# DAC2.net
KiCad netlist of a schematic drawn in EAGLE
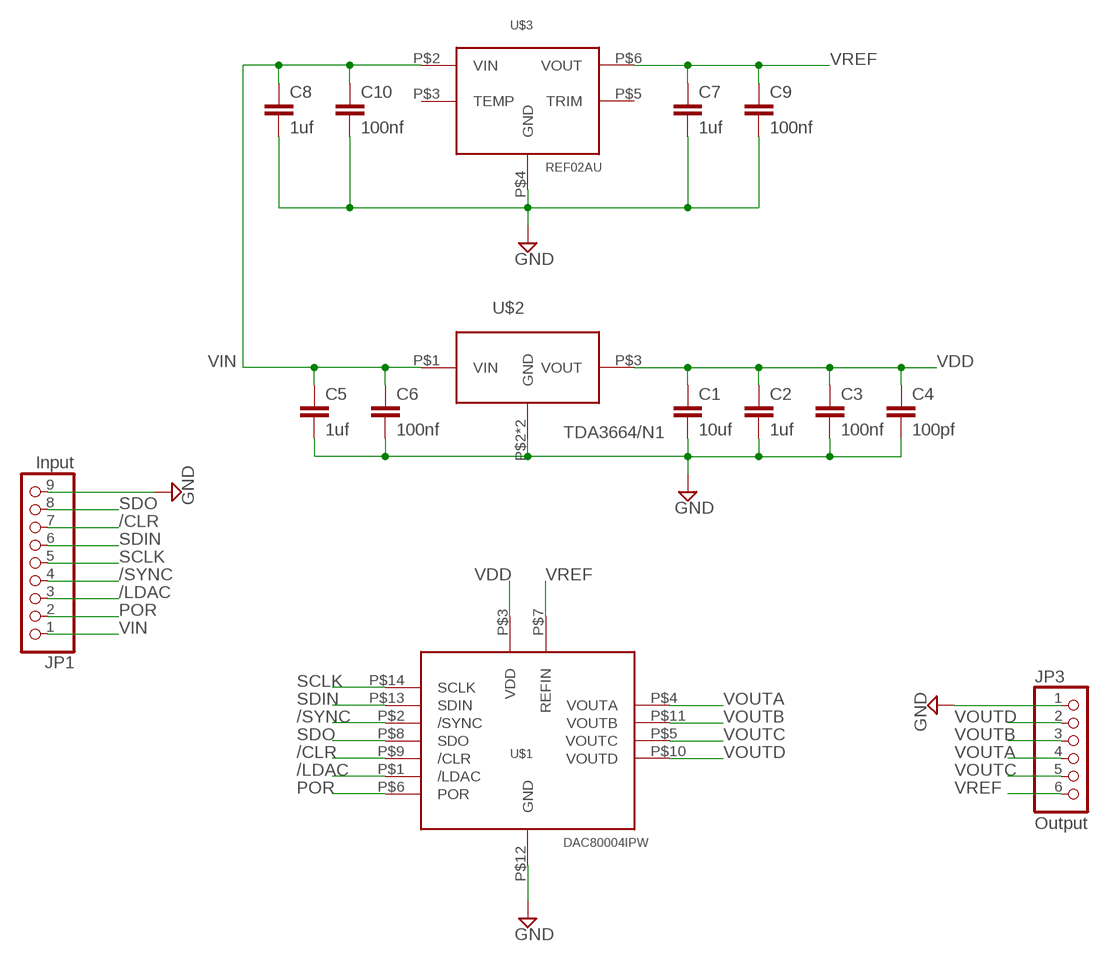
[diagram p0: schematic, sheet 1]

(export (version "E")
  (design (tool "Eeschema 10.0.6"))
  (components
    (comp (ref "C1")
      (value "10uf")
      (footprint "eagle-import:C1210")
      (libsource (lib "eagle-import") (part "C-EUC1210"))
    )
    (comp (ref "C2")
      (value "1uf")
      (footprint "eagle-import:C0603")
      (libsource (lib "eagle-import") (part "C-EUC0603"))
    )
    (comp (ref "C3")
      (value "100nf")
      (footprint "eagle-import:C0603")
      (libsource (lib "eagle-import") (part "C-EUC0603"))
    )
    (comp (ref "C4")
      (value "100pf")
      (footprint "eagle-import:C0603")
      (libsource (lib "eagle-import") (part "C-EUC0603"))
    )
    (comp (ref "C5")
      (value "1uf")
      (footprint "eagle-import:C0603")
      (libsource (lib "eagle-import") (part "C-EUC0603"))
    )
    (comp (ref "C6")
      (value "100nf")
      (footprint "eagle-import:C0603")
      (libsource (lib "eagle-import") (part "C-EUC0603"))
    )
    (comp (ref "C7")
      (value "1uf")
      (footprint "eagle-import:C0603")
      (libsource (lib "eagle-import") (part "C-EUC0603"))
    )
    (comp (ref "C8")
      (value "1uf")
      (footprint "eagle-import:C0603")
      (libsource (lib "eagle-import") (part "C-EUC0603"))
    )
    (comp (ref "C9")
      (value "100nf")
      (footprint "eagle-import:C0603")
      (libsource (lib "eagle-import") (part "C-EUC0603"))
    )
    (comp (ref "C10")
      (value "100nf")
      (footprint "eagle-import:C0603")
      (libsource (lib "eagle-import") (part "C-EUC0603"))
    )
    (comp (ref "JP1")
      (value "Input")
      (footprint "eagle-import:1X09")
      (libsource (lib "eagle-import") (part "PINHD-1X9"))
    )
    (comp (ref "JP3")
      (value "Output")
      (footprint "eagle-import:1X06")
      (libsource (lib "eagle-import") (part "PINHD-1X6"))
    )
    (comp (ref "U$1")
      (value "DAC80004IPW")
      (footprint "eagle-import:TSSOP14")
      (libsource (lib "eagle-import") (part "DAC80004IPW"))
    )
    (comp (ref "U$2")
      (value "TDA3664/N1")
      (footprint "eagle-import:SOT223")
      (libsource (lib "eagle-import") (part "TDA3664/N1"))
    )
    (comp (ref "U$3")
      (value "REF02AU")
      (footprint "eagle-import:SO8")
      (libsource (lib "eagle-import") (part "REF02AU"))
    )
  )
  (nets
    (net (code "1") (name "/POR") (class "Default")
      (node (ref "JP1") (pin "2") (pinfunction "2_2") (pintype "passive"))
      (node (ref "U$1") (pin "P$6") (pinfunction "POR_P$6") (pintype "input"))
    )
    (net (code "2") (name "/SCLK") (class "Default")
      (node (ref "JP1") (pin "5") (pinfunction "5_5") (pintype "passive"))
      (node (ref "U$1") (pin "P$14") (pinfunction "SCLK_P$14") (pintype "input"))
    )
    (net (code "3") (name "/SDIN") (class "Default")
      (node (ref "JP1") (pin "6") (pinfunction "6_6") (pintype "passive"))
      (node (ref "U$1") (pin "P$13") (pinfunction "SDIN_P$13") (pintype "input"))
    )
    (net (code "4") (name "/SDO") (class "Default")
      (node (ref "JP1") (pin "8") (pinfunction "8_8") (pintype "passive"))
      (node (ref "U$1") (pin "P$8") (pinfunction "SDO_P$8") (pintype "output"))
    )
    (net (code "5") (name "/VDD") (class "Default")
      (node (ref "C1") (pin "1") (pinfunction "1_1") (pintype "passive"))
      (node (ref "C2") (pin "1") (pinfunction "1_1") (pintype "passive"))
      (node (ref "C3") (pin "1") (pinfunction "1_1") (pintype "passive"))
      (node (ref "C4") (pin "1") (pinfunction "1_1") (pintype "passive"))
      (node (ref "U$1") (pin "P$3") (pinfunction "VDD_P$3") (pintype "power_in"))
      (node (ref "U$2") (pin "P$3") (pinfunction "VOUT_P$3") (pintype "output"))
    )
    (net (code "6") (name "/VIN") (class "Default")
      (node (ref "C10") (pin "1") (pinfunction "1_1") (pintype "passive"))
      (node (ref "C5") (pin "1") (pinfunction "1_1") (pintype "passive"))
      (node (ref "C6") (pin "1") (pinfunction "1_1") (pintype "passive"))
      (node (ref "C8") (pin "1") (pinfunction "1_1") (pintype "passive"))
      (node (ref "JP1") (pin "1") (pinfunction "1_1") (pintype "passive"))
      (node (ref "U$2") (pin "P$1") (pinfunction "VIN_P$1") (pintype "power_in"))
      (node (ref "U$3") (pin "P$2") (pinfunction "VIN_P$2") (pintype "power_in"))
    )
    (net (code "7") (name "/VOUTA") (class "Default")
      (node (ref "JP3") (pin "4") (pinfunction "4_4") (pintype "passive"))
      (node (ref "U$1") (pin "P$4") (pinfunction "VOUTA_P$4") (pintype "output"))
    )
    (net (code "8") (name "/VOUTB") (class "Default")
      (node (ref "JP3") (pin "3") (pinfunction "3_3") (pintype "passive"))
      (node (ref "U$1") (pin "P$11") (pinfunction "VOUTB_P$11") (pintype "output"))
    )
    (net (code "9") (name "/VOUTC") (class "Default")
      (node (ref "JP3") (pin "5") (pinfunction "5_5") (pintype "passive"))
      (node (ref "U$1") (pin "P$5") (pinfunction "VOUTC_P$5") (pintype "output"))
    )
    (net (code "10") (name "/VOUTD") (class "Default")
      (node (ref "JP3") (pin "2") (pinfunction "2_2") (pintype "passive"))
      (node (ref "U$1") (pin "P$10") (pinfunction "VOUTD_P$10") (pintype "output"))
    )
    (net (code "11") (name "/VREF") (class "Default")
      (node (ref "C7") (pin "1") (pinfunction "1_1") (pintype "passive"))
      (node (ref "C9") (pin "1") (pinfunction "1_1") (pintype "passive"))
      (node (ref "JP3") (pin "6") (pinfunction "6_6") (pintype "passive"))
      (node (ref "U$1") (pin "P$7") (pinfunction "REFIN_P$7") (pintype "input"))
      (node (ref "U$3") (pin "P$6") (pinfunction "VOUT_P$6") (pintype "output"))
    )
    (net (code "12") (name "/{slash}CLR") (class "Default")
      (node (ref "JP1") (pin "7") (pinfunction "7_7") (pintype "passive"))
      (node (ref "U$1") (pin "P$9") (pinfunction "/CLR_P$9") (pintype "input"))
    )
    (net (code "13") (name "/{slash}LDAC") (class "Default")
      (node (ref "JP1") (pin "3") (pinfunction "3_3") (pintype "passive"))
      (node (ref "U$1") (pin "P$1") (pinfunction "/LDAC_P$1") (pintype "input"))
    )
    (net (code "14") (name "/{slash}SYNC") (class "Default")
      (node (ref "JP1") (pin "4") (pinfunction "4_4") (pintype "passive"))
      (node (ref "U$1") (pin "P$2") (pinfunction "/SYNC_P$2") (pintype "input"))
    )
    (net (code "15") (name "GND") (class "Default")
      (node (ref "C1") (pin "2") (pinfunction "2_2") (pintype "passive"))
      (node (ref "C10") (pin "2") (pinfunction "2_2") (pintype "passive"))
      (node (ref "C2") (pin "2") (pinfunction "2_2") (pintype "passive"))
      (node (ref "C3") (pin "2") (pinfunction "2_2") (pintype "passive"))
      (node (ref "C4") (pin "2") (pinfunction "2_2") (pintype "passive"))
      (node (ref "C5") (pin "2") (pinfunction "2_2") (pintype "passive"))
      (node (ref "C6") (pin "2") (pinfunction "2_2") (pintype "passive"))
      (node (ref "C7") (pin "2") (pinfunction "2_2") (pintype "passive"))
      (node (ref "C8") (pin "2") (pinfunction "2_2") (pintype "passive"))
      (node (ref "C9") (pin "2") (pinfunction "2_2") (pintype "passive"))
      (node (ref "JP1") (pin "9") (pinfunction "9_9") (pintype "passive"))
      (node (ref "JP3") (pin "1") (pinfunction "1_1") (pintype "passive"))
      (node (ref "U$1") (pin "P$12") (pinfunction "GND_P$12") (pintype "power_in"))
      (node (ref "U$2") (pin "P$2") (pinfunction "GND_P$2") (pintype "power_in"))
      (node (ref "U$2") (pin "P$4") (pinfunction "GND_P$4") (pintype "power_in"))
      (node (ref "U$3") (pin "P$4") (pinfunction "GND_P$4") (pintype "power_in"))
    )
    (net (code "16") (name "unconnected-(U$3-TEMP-PadP$3)") (class "Default")
      (node (ref "U$3") (pin "P$3") (pinfunction "TEMP_P$3") (pintype "bidirectional"))
    )
    (net (code "17") (name "unconnected-(U$3-TRIM-PadP$5)") (class "Default")
      (node (ref "U$3") (pin "P$5") (pinfunction "TRIM_P$5") (pintype "bidirectional"))
    )
  )
)
